# class_d_amplifier.net
KiCad netlist of a schematic drawn in EAGLE
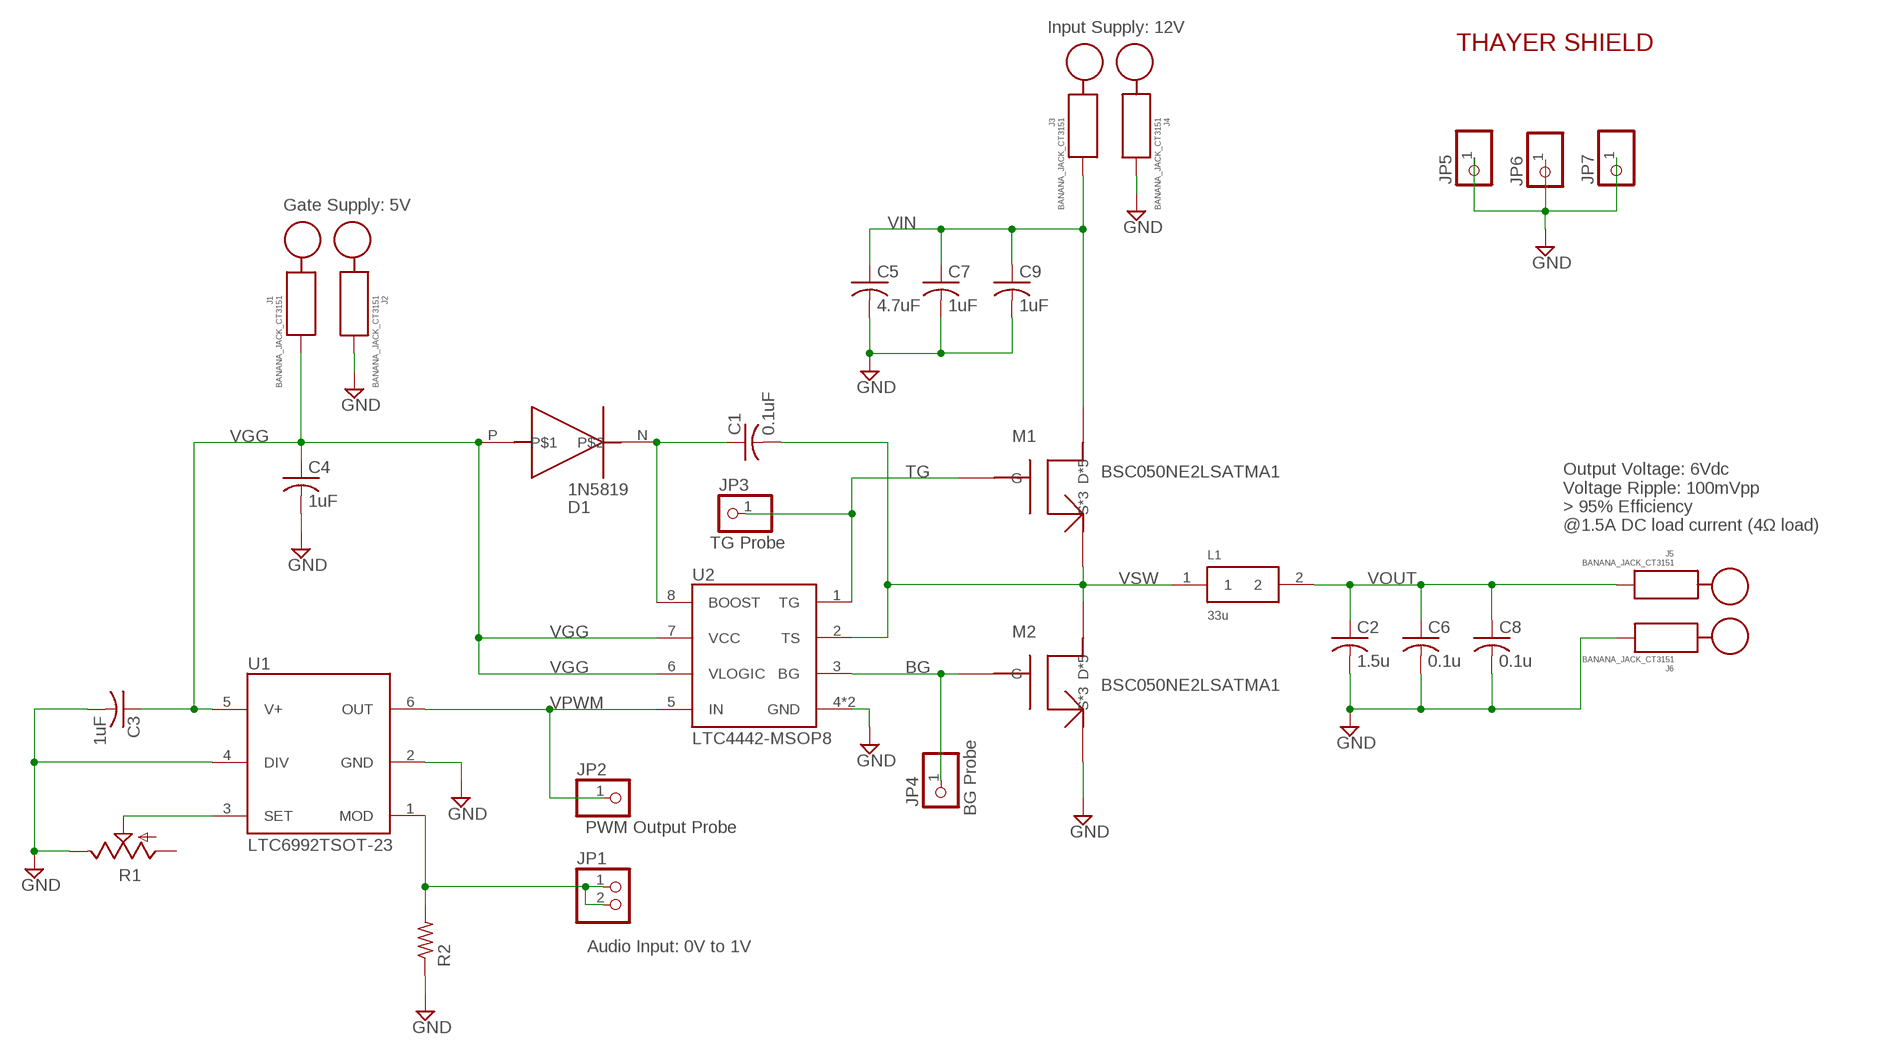
[diagram p0: schematic, sheet 1]

(export (version "E")
  (design (tool "Eeschema 10.0.6"))
  (components
    (comp (ref "C1")
      (value "0.1uF")
      (footprint "eagle-import:C0805")
      (libsource (lib "eagle-import") (part "C-US"))
    )
    (comp (ref "C2")
      (value "1.5u")
      (footprint "eagle-import:C1206")
      (libsource (lib "eagle-import") (part "C-USC1206"))
    )
    (comp (ref "C3")
      (value "1uF")
      (footprint "eagle-import:C0805")
      (libsource (lib "eagle-import") (part "C-US"))
    )
    (comp (ref "C4")
      (value "1uF")
      (footprint "eagle-import:C0805")
      (libsource (lib "eagle-import") (part "C-US"))
    )
    (comp (ref "C5")
      (value "4.7uF")
      (footprint "eagle-import:C1206")
      (libsource (lib "eagle-import") (part "C-USC1206"))
    )
    (comp (ref "C6")
      (value "0.1u")
      (footprint "eagle-import:C0805")
      (libsource (lib "eagle-import") (part "C-US"))
    )
    (comp (ref "C7")
      (value "1uF")
      (footprint "eagle-import:C0805")
      (libsource (lib "eagle-import") (part "C-US"))
    )
    (comp (ref "C8")
      (value "0.1u")
      (footprint "eagle-import:C0805")
      (libsource (lib "eagle-import") (part "C-US"))
    )
    (comp (ref "C9")
      (value "1uF")
      (footprint "eagle-import:C0805")
      (libsource (lib "eagle-import") (part "C-US"))
    )
    (comp (ref "D1")
      (value "1N5819")
      (footprint "eagle-import:SOD123")
      (libsource (lib "eagle-import") (part "DIODE"))
    )
    (comp (ref "J1")
      (value "BANANA_JACK_CT3151")
      (footprint "eagle-import:CT3151SP2_PCB_MOUNT")
      (libsource (lib "eagle-import") (part "BANANA_JACK_CT3151"))
    )
    (comp (ref "J2")
      (value "BANANA_JACK_CT3151")
      (footprint "eagle-import:CT3151SP2_PCB_MOUNT")
      (libsource (lib "eagle-import") (part "BANANA_JACK_CT3151"))
    )
    (comp (ref "J3")
      (value "BANANA_JACK_CT3151")
      (footprint "eagle-import:CT3151SP2_PCB_MOUNT")
      (libsource (lib "eagle-import") (part "BANANA_JACK_CT3151"))
    )
    (comp (ref "J4")
      (value "BANANA_JACK_CT3151")
      (footprint "eagle-import:CT3151SP2_PCB_MOUNT")
      (libsource (lib "eagle-import") (part "BANANA_JACK_CT3151"))
    )
    (comp (ref "J5")
      (value "BANANA_JACK_CT3151")
      (footprint "eagle-import:CT3151SP2_PCB_MOUNT")
      (libsource (lib "eagle-import") (part "BANANA_JACK_CT3151"))
    )
    (comp (ref "J6")
      (value "BANANA_JACK_CT3151")
      (footprint "eagle-import:CT3151SP2_PCB_MOUNT")
      (libsource (lib "eagle-import") (part "BANANA_JACK_CT3151"))
    )
    (comp (ref "JP1")
      (value "PINHD-1X2")
      (footprint "eagle-import:1X02")
      (libsource (lib "eagle-import") (part "PINHD-1X2"))
    )
    (comp (ref "JP2")
      (value "PINHD-1X1")
      (footprint "eagle-import:1X01")
      (libsource (lib "eagle-import") (part "PINHD-1X1"))
    )
    (comp (ref "JP3")
      (value "PINHD-1X1")
      (footprint "eagle-import:1X01")
      (libsource (lib "eagle-import") (part "PINHD-1X1"))
    )
    (comp (ref "JP4")
      (value "PINHD-1X1")
      (footprint "eagle-import:1X01")
      (libsource (lib "eagle-import") (part "PINHD-1X1"))
    )
    (comp (ref "JP5")
      (value "PINHD-1X1")
      (footprint "eagle-import:1X01")
      (libsource (lib "eagle-import") (part "PINHD-1X1"))
    )
    (comp (ref "JP6")
      (value "PINHD-1X1")
      (footprint "eagle-import:1X01")
      (libsource (lib "eagle-import") (part "PINHD-1X1"))
    )
    (comp (ref "JP7")
      (value "PINHD-1X1")
      (footprint "eagle-import:1X01")
      (libsource (lib "eagle-import") (part "PINHD-1X1"))
    )
    (comp (ref "L1")
      (value "33u")
      (footprint "eagle-import:SER2900")
      (libsource (lib "eagle-import") (part "SER2900SER"))
    )
    (comp (ref "M1")
      (value "BSC050NE2LSATMA1")
      (footprint "eagle-import:PD-TDSON-8")
      (libsource (lib "eagle-import") (part "BSC050NE2LSATMA1"))
    )
    (comp (ref "M2")
      (value "BSC050NE2LSATMA1")
      (footprint "eagle-import:PD-TDSON-8")
      (libsource (lib "eagle-import") (part "BSC050NE2LSATMA1"))
    )
    (comp (ref "R1")
      (value "TRIM_US-CT6")
      (footprint "eagle-import:CT6")
      (libsource (lib "eagle-import") (part "TRIM_US-CT6"))
    )
    (comp (ref "R2")
      (value "R-US")
      (footprint "eagle-import:R0805")
      (libsource (lib "eagle-import") (part "R-US"))
    )
    (comp (ref "U$1")
      (value "THAYER")
      (footprint "eagle-import:THAYER")
      (libsource (lib "eagle-import") (part "THAYER"))
    )
    (comp (ref "U1")
      (value "LTC6992TSOT-23")
      (footprint "eagle-import:TSOT23-6")
      (libsource (lib "eagle-import") (part "LTC6992TSOT-23"))
    )
    (comp (ref "U2")
      (value "LTC4442-MSOP8")
      (footprint "eagle-import:LTC4442")
      (libsource (lib "eagle-import") (part "LTC4442"))
    )
  )
  (nets
    (net (code "1") (name "/BG") (class "Default")
      (node (ref "JP4") (pin "1") (pinfunction "1_1") (pintype "passive"))
      (node (ref "M2") (pin "4") (pinfunction "G_4") (pintype "bidirectional"))
      (node (ref "U2") (pin "3") (pinfunction "BG_3") (pintype "bidirectional"))
    )
    (net (code "2") (name "/TG") (class "Default")
      (node (ref "JP3") (pin "1") (pinfunction "1_1") (pintype "passive"))
      (node (ref "M1") (pin "4") (pinfunction "G_4") (pintype "bidirectional"))
      (node (ref "U2") (pin "1") (pinfunction "TG_1") (pintype "bidirectional"))
    )
    (net (code "3") (name "/VGG") (class "Default")
      (node (ref "C3") (pin "1") (pinfunction "1_1") (pintype "passive"))
      (node (ref "C4") (pin "1") (pinfunction "1_1") (pintype "passive"))
      (node (ref "D1") (pin "P") (pinfunction "P$1_P") (pintype "bidirectional"))
      (node (ref "J1") (pin "P$1") (pinfunction "IN_P$1") (pintype "bidirectional"))
      (node (ref "J1") (pin "P$2") (pinfunction "IN_P$2") (pintype "bidirectional"))
      (node (ref "J1") (pin "P$3") (pinfunction "IN_P$3") (pintype "bidirectional"))
      (node (ref "J1") (pin "P$4") (pinfunction "IN_P$4") (pintype "bidirectional"))
      (node (ref "U1") (pin "5") (pinfunction "V+_5") (pintype "bidirectional"))
      (node (ref "U2") (pin "6") (pinfunction "VLOGIC_6") (pintype "bidirectional"))
      (node (ref "U2") (pin "7") (pinfunction "VCC_7") (pintype "bidirectional"))
    )
    (net (code "4") (name "/VIN") (class "Default")
      (node (ref "C5") (pin "1") (pinfunction "1_1") (pintype "passive"))
      (node (ref "C7") (pin "1") (pinfunction "1_1") (pintype "passive"))
      (node (ref "C9") (pin "1") (pinfunction "1_1") (pintype "passive"))
      (node (ref "J3") (pin "P$1") (pinfunction "IN_P$1") (pintype "bidirectional"))
      (node (ref "J3") (pin "P$2") (pinfunction "IN_P$2") (pintype "bidirectional"))
      (node (ref "J3") (pin "P$3") (pinfunction "IN_P$3") (pintype "bidirectional"))
      (node (ref "J3") (pin "P$4") (pinfunction "IN_P$4") (pintype "bidirectional"))
      (node (ref "M1") (pin "5") (pinfunction "D*5_5") (pintype "bidirectional"))
      (node (ref "M1") (pin "6") (pinfunction "D*5_6") (pintype "bidirectional"))
      (node (ref "M1") (pin "7") (pinfunction "D*5_7") (pintype "bidirectional"))
      (node (ref "M1") (pin "8") (pinfunction "D*5_8") (pintype "bidirectional"))
      (node (ref "M1") (pin "9") (pinfunction "D*5_9") (pintype "bidirectional"))
    )
    (net (code "5") (name "/VOUT") (class "Default")
      (node (ref "C2") (pin "1") (pinfunction "1_1") (pintype "passive"))
      (node (ref "C6") (pin "1") (pinfunction "1_1") (pintype "passive"))
      (node (ref "C8") (pin "1") (pinfunction "1_1") (pintype "passive"))
      (node (ref "J5") (pin "P$1") (pinfunction "IN_P$1") (pintype "bidirectional"))
      (node (ref "J5") (pin "P$2") (pinfunction "IN_P$2") (pintype "bidirectional"))
      (node (ref "J5") (pin "P$3") (pinfunction "IN_P$3") (pintype "bidirectional"))
      (node (ref "J5") (pin "P$4") (pinfunction "IN_P$4") (pintype "bidirectional"))
      (node (ref "L1") (pin "2") (pinfunction "2_2") (pintype "bidirectional"))
    )
    (net (code "6") (name "/VPWM") (class "Default")
      (node (ref "JP2") (pin "1") (pinfunction "1_1") (pintype "passive"))
      (node (ref "U1") (pin "6") (pinfunction "OUT_6") (pintype "bidirectional"))
      (node (ref "U2") (pin "5") (pinfunction "IN_5") (pintype "bidirectional"))
    )
    (net (code "7") (name "/VSW") (class "Default")
      (node (ref "C1") (pin "2") (pinfunction "2_2") (pintype "passive"))
      (node (ref "L1") (pin "1") (pinfunction "1_1") (pintype "bidirectional"))
      (node (ref "M1") (pin "1") (pinfunction "S*3_1") (pintype "bidirectional"))
      (node (ref "M1") (pin "2") (pinfunction "S*3_2") (pintype "bidirectional"))
      (node (ref "M1") (pin "3") (pinfunction "S*3_3") (pintype "bidirectional"))
      (node (ref "M2") (pin "5") (pinfunction "D*5_5") (pintype "bidirectional"))
      (node (ref "M2") (pin "6") (pinfunction "D*5_6") (pintype "bidirectional"))
      (node (ref "M2") (pin "7") (pinfunction "D*5_7") (pintype "bidirectional"))
      (node (ref "M2") (pin "8") (pinfunction "D*5_8") (pintype "bidirectional"))
      (node (ref "M2") (pin "9") (pinfunction "D*5_9") (pintype "bidirectional"))
      (node (ref "U2") (pin "2") (pinfunction "TS_2") (pintype "bidirectional"))
    )
    (net (code "8") (name "GND") (class "Default")
      (node (ref "C2") (pin "2") (pinfunction "2_2") (pintype "passive"))
      (node (ref "C3") (pin "2") (pinfunction "2_2") (pintype "passive"))
      (node (ref "C4") (pin "2") (pinfunction "2_2") (pintype "passive"))
      (node (ref "C5") (pin "2") (pinfunction "2_2") (pintype "passive"))
      (node (ref "C6") (pin "2") (pinfunction "2_2") (pintype "passive"))
      (node (ref "C7") (pin "2") (pinfunction "2_2") (pintype "passive"))
      (node (ref "C8") (pin "2") (pinfunction "2_2") (pintype "passive"))
      (node (ref "C9") (pin "2") (pinfunction "2_2") (pintype "passive"))
      (node (ref "J2") (pin "P$1") (pinfunction "IN_P$1") (pintype "bidirectional"))
      (node (ref "J2") (pin "P$2") (pinfunction "IN_P$2") (pintype "bidirectional"))
      (node (ref "J2") (pin "P$3") (pinfunction "IN_P$3") (pintype "bidirectional"))
      (node (ref "J2") (pin "P$4") (pinfunction "IN_P$4") (pintype "bidirectional"))
      (node (ref "J4") (pin "P$1") (pinfunction "IN_P$1") (pintype "bidirectional"))
      (node (ref "J4") (pin "P$2") (pinfunction "IN_P$2") (pintype "bidirectional"))
      (node (ref "J4") (pin "P$3") (pinfunction "IN_P$3") (pintype "bidirectional"))
      (node (ref "J4") (pin "P$4") (pinfunction "IN_P$4") (pintype "bidirectional"))
      (node (ref "J6") (pin "P$1") (pinfunction "IN_P$1") (pintype "bidirectional"))
      (node (ref "J6") (pin "P$2") (pinfunction "IN_P$2") (pintype "bidirectional"))
      (node (ref "J6") (pin "P$3") (pinfunction "IN_P$3") (pintype "bidirectional"))
      (node (ref "J6") (pin "P$4") (pinfunction "IN_P$4") (pintype "bidirectional"))
      (node (ref "JP5") (pin "1") (pinfunction "1_1") (pintype "passive"))
      (node (ref "JP6") (pin "1") (pinfunction "1_1") (pintype "passive"))
      (node (ref "JP7") (pin "1") (pinfunction "1_1") (pintype "passive"))
      (node (ref "M2") (pin "1") (pinfunction "S*3_1") (pintype "bidirectional"))
      (node (ref "M2") (pin "2") (pinfunction "S*3_2") (pintype "bidirectional"))
      (node (ref "M2") (pin "3") (pinfunction "S*3_3") (pintype "bidirectional"))
      (node (ref "R1") (pin "E") (pinfunction "E_E") (pintype "passive"))
      (node (ref "R2") (pin "1") (pinfunction "1_1") (pintype "passive"))
      (node (ref "U1") (pin "2") (pinfunction "GND_2") (pintype "bidirectional"))
      (node (ref "U1") (pin "4") (pinfunction "DIV_4") (pintype "bidirectional"))
      (node (ref "U2") (pin "4") (pinfunction "GND_4") (pintype "bidirectional"))
      (node (ref "U2") (pin "9") (pinfunction "GND_9") (pintype "bidirectional"))
    )
    (net (code "9") (name "Net-(D1-P$2)") (class "Default")
      (node (ref "C1") (pin "1") (pinfunction "1_1") (pintype "passive"))
      (node (ref "D1") (pin "N") (pinfunction "P$2_N") (pintype "bidirectional"))
      (node (ref "U2") (pin "8") (pinfunction "BOOST_8") (pintype "bidirectional"))
    )
    (net (code "10") (name "Net-(U1-MOD)") (class "Default")
      (node (ref "JP1") (pin "1") (pinfunction "1_1") (pintype "passive"))
      (node (ref "JP1") (pin "2") (pinfunction "2_2") (pintype "passive"))
      (node (ref "R2") (pin "2") (pinfunction "2_2") (pintype "passive"))
      (node (ref "U1") (pin "1") (pinfunction "MOD_1") (pintype "bidirectional"))
    )
    (net (code "11") (name "Net-(U1-SET)") (class "Default")
      (node (ref "R1") (pin "S") (pinfunction "S_S") (pintype "passive"))
      (node (ref "U1") (pin "3") (pinfunction "SET_3") (pintype "bidirectional"))
    )
    (net (code "12") (name "unconnected-(R1-PadA)") (class "Default")
      (node (ref "R1") (pin "A") (pinfunction "A_A") (pintype "passive"))
    )
  )
)
